# 02_ESP32-S2_Module.net
KiCad netlist of a schematic drawn in Altium Designer
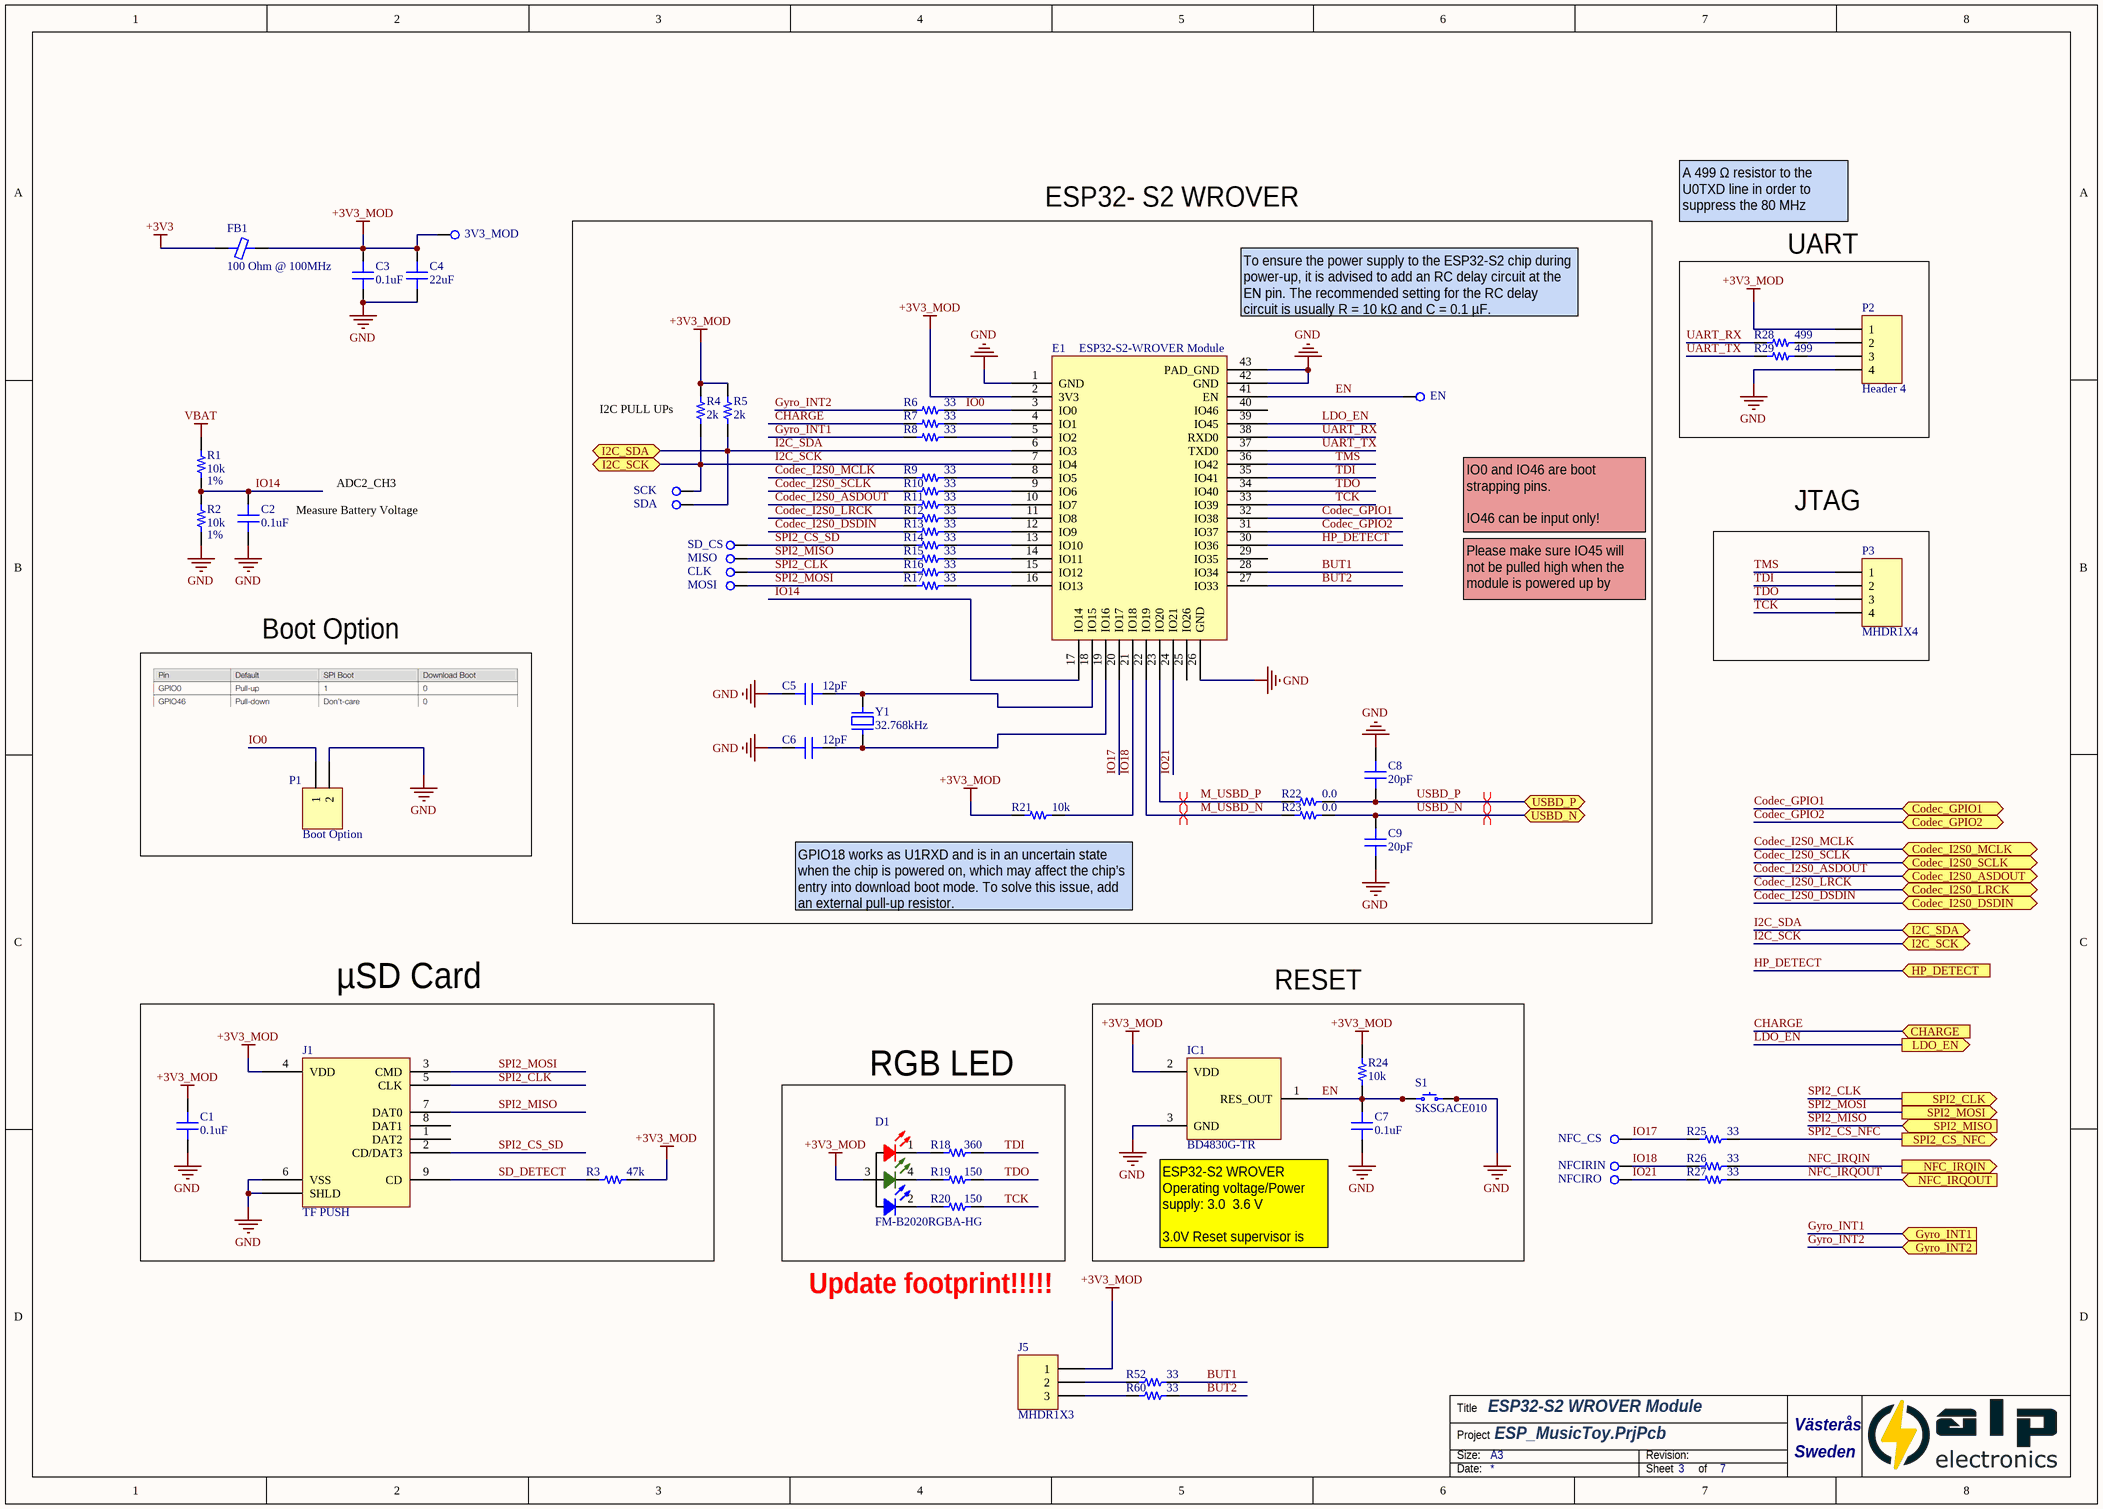
[diagram p0: [02] ESP32-S2 Module.SchDoc]

(export (version "E")
  (design (tool "Eeschema 10.0.6"))
  (components
    (comp (ref "3V3_MOD")
      (value "RCT-0C")
      (footprint "TE TP 0805")
      (description "0805 PROBE PAD")
      (fields (field (name "MANUFACTURER") "TE Connectivity AMP Connectors"))
      (libsource (lib "Celestial Library Database") (part "Test Point"))
    )
    (comp (ref "C1")
      (value "0.1uF")
      (footprint "CAP 0402/1005")
      (description "CAP CER 0.1UF 10V X7R 0402")
      (fields
        (field (name "PART NUMBER") "C1005X7R1A104K050BB")
        (field (name "MANUFACTURER") "TDK Corporation")
      )
      (libsource (lib "Celestial Library Database") (part "Capacitor"))
    )
    (comp (ref "C2")
      (value "0.1uF")
      (footprint "CAP 0402/1005")
      (description "CAP CER 0.1UF 10V X7R 0402")
      (fields
        (field (name "PART NUMBER") "C1005X7R1A104K050BB")
        (field (name "MANUFACTURER") "TDK Corporation")
      )
      (libsource (lib "Celestial Library Database") (part "Capacitor"))
    )
    (comp (ref "C3")
      (value "0.1uF")
      (footprint "CAP 0402/1005")
      (description "CAP CER 0.1UF 10V X7R 0402")
      (fields
        (field (name "PART NUMBER") "C1005X7R1A104K050BB")
        (field (name "MANUFACTURER") "TDK Corporation")
      )
      (libsource (lib "Celestial Library Database") (part "Capacitor"))
    )
    (comp (ref "C4")
      (value "22uF")
      (footprint "CAP 0603/1608")
      (description "CAP CER 22UF 10V X5R 0603")
      (fields
        (field (name "PART NUMBER") "C1608X5R1A226M080AC")
        (field (name "MANUFACTURER") "TDK Corporation")
      )
      (libsource (lib "Celestial Library Database") (part "Capacitor"))
    )
    (comp (ref "C5")
      (value "12pF")
      (footprint "CAP 0402/1005")
      (description "CAP CER 12PF 25V NP0 0402")
      (fields
        (field (name "PART NUMBER") "GRM1555C1E120JA01D")
        (field (name "MANUFACTURER") "Murata Electronics North America")
      )
      (libsource (lib "Celestial Library Database") (part "Capacitor"))
    )
    (comp (ref "C6")
      (value "12pF")
      (footprint "CAP 0402/1005")
      (description "CAP CER 12PF 25V NP0 0402")
      (fields
        (field (name "PART NUMBER") "GRM1555C1E120JA01D")
        (field (name "MANUFACTURER") "Murata Electronics North America")
      )
      (libsource (lib "Celestial Library Database") (part "Capacitor"))
    )
    (comp (ref "C7")
      (value "0.1uF")
      (footprint "CAP 0402/1005")
      (description "CAP CER 0.1UF 10V X7R 0402")
      (fields
        (field (name "PART NUMBER") "C1005X7R1A104K050BB")
        (field (name "MANUFACTURER") "TDK Corporation")
      )
      (libsource (lib "Celestial Library Database") (part "Capacitor"))
    )
    (comp (ref "C8")
      (value "20pF")
      (footprint "CAP 0402/1005")
      (description "CAP CER 20PF 25V NP0 0402")
      (fields
        (field (name "PART NUMBER") "GRM1555C1E200JA01D")
        (field (name "MANUFACTURER") "Murata Electronics North America")
      )
      (libsource (lib "Celestial Library Database") (part "Capacitor"))
    )
    (comp (ref "C9")
      (value "20pF")
      (footprint "CAP 0402/1005")
      (description "CAP CER 20PF 25V NP0 0402")
      (fields
        (field (name "PART NUMBER") "GRM1555C1E200JA01D")
        (field (name "MANUFACTURER") "Murata Electronics North America")
      )
      (libsource (lib "Celestial Library Database") (part "Capacitor"))
    )
    (comp (ref "CLK")
      (value "RCT-0C")
      (footprint "3D FootPrint_Backup:0.5mm-TestPad")
      (description "0805 PROBE PAD")
      (fields (field (name "MANUFACTURER") "TE Connectivity AMP Connectors"))
      (libsource (lib "Celestial Library Database") (part "Test Point"))
    )
    (comp (ref "D1")
      (value "FM-B2020RGBA-HG")
      (footprint "FM-B2020RGBA-HG")
      (description "RGB 615~630nmRed,515~535nmGreen,465~480nmBlue 2020")
      (fields (field (name "MANUFACTURER") "Foshan NationStar Optoelectronics"))
      (libsource (lib "Celestial Library Database") (part "RGB LED 4PIN"))
    )
    (comp (ref "E1")
      (value "ESP32-S2-WROVER Module")
      (footprint "ESP32-S2-WROVER")
      (libsource (lib "Altium Component") (part "ESP32-S2-WROVER Module"))
    )
    (comp (ref "EN")
      (value "RCT-0C")
      (footprint "3D FootPrint_Backup:0.5mm-TestPad")
      (description "0805 PROBE PAD")
      (fields (field (name "MANUFACTURER") "TE Connectivity AMP Connectors"))
      (libsource (lib "Celestial Library Database") (part "Test Point"))
    )
    (comp (ref "FB1")
      (value "100 Ohm @ 100MHz")
      (footprint "FER 0805/2012")
      (description "FERRITE CHIP 100 OHM 2000MA 0805")
      (fields
        (field (name "PART NUMBER") "CIC21P101NE")
        (field (name "MANUFACTURER") "Samsung Electro-Mechanics America, Inc.")
      )
      (libsource (lib "Celestial Library Database") (part "Ferrite Chip"))
    )
    (comp (ref "IC1")
      (value "BD4830G-TR")
      (footprint "TI SOT-23-5 DBV")
      (description "IC MPU RESET CIRC 3V SOT23-5")
      (fields (field (name "MANUFACTURER") "ROHM Semiconductor"))
      (libsource (lib "Celestial Library Database") (part "BD4830G"))
    )
    (comp (ref "J1")
      (value "TF PUSH")
      (footprint "TF-PUSH")
      (description "MICRO SD PUSH/PUSH SMALL 8C")
      (fields (field (name "MANUFACTURER") "SHOU HAN"))
      (libsource (lib "Celestial Library Database") (part "TF PUSH"))
    )
    (comp (ref "J5")
      (value "MHDR1X3")
      (footprint "MHDR1X3")
      (description "Header, 3-Pin")
      (fields (field (name "PUBLISHER") "Altium Limited"))
      (libsource (lib "Miscellaneous Connectors") (part "MHDR1X3"))
    )
    (comp (ref "MISO")
      (value "RCT-0C")
      (footprint "3D FootPrint_Backup:0.5mm-TestPad")
      (description "0805 PROBE PAD")
      (fields (field (name "MANUFACTURER") "TE Connectivity AMP Connectors"))
      (libsource (lib "Celestial Library Database") (part "Test Point"))
    )
    (comp (ref "MOSI")
      (value "RCT-0C")
      (footprint "3D FootPrint_Backup:0.5mm-TestPad")
      (description "0805 PROBE PAD")
      (fields (field (name "MANUFACTURER") "TE Connectivity AMP Connectors"))
      (libsource (lib "Celestial Library Database") (part "Test Point"))
    )
    (comp (ref "NFCIRIN")
      (value "RCT-0C")
      (footprint "3D FootPrint_Backup:0.5mm-TestPad")
      (description "0805 PROBE PAD")
      (fields (field (name "MANUFACTURER") "TE Connectivity AMP Connectors"))
      (libsource (lib "Celestial Library Database") (part "Test Point"))
    )
    (comp (ref "NFCIRO")
      (value "RCT-0C")
      (footprint "3D FootPrint_Backup:0.5mm-TestPad")
      (description "0805 PROBE PAD")
      (fields (field (name "MANUFACTURER") "TE Connectivity AMP Connectors"))
      (libsource (lib "Celestial Library Database") (part "Test Point"))
    )
    (comp (ref "NFC_CS")
      (value "RCT-0C")
      (footprint "3D FootPrint_Backup:0.5mm-TestPad")
      (description "0805 PROBE PAD")
      (fields (field (name "MANUFACTURER") "TE Connectivity AMP Connectors"))
      (libsource (lib "Celestial Library Database") (part "Test Point"))
    )
    (comp (ref "P1")
      (value "Boot Option")
      (footprint "HDR1X2")
      (description "Header, 2-Pin")
      (fields (field (name "PUBLISHER") "Altium Limited"))
      (libsource (lib "Miscellaneous Connectors") (part "Header 2"))
    )
    (comp (ref "P2")
      (value "Header 4")
      (footprint "HDR1X4")
      (description "Header, 4-Pin")
      (fields (field (name "PUBLISHER") "Altium Limited"))
      (libsource (lib "Miscellaneous Connectors") (part "Header 4"))
    )
    (comp (ref "P3")
      (value "MHDR1X4")
      (footprint "MHDR1X4")
      (description "Header, 4-Pin")
      (fields (field (name "PUBLISHER") "Altium Limited"))
      (libsource (lib "Miscellaneous Connectors") (part "MHDR1X4"))
    )
    (comp (ref "R1")
      (value "10k")
      (footprint "RES 0402/1005")
      (description "RES SMD 10K OHM 1% 1/10W 0402")
      (fields
        (field (name "PART NUMBER") "ERJ-2RKF1002X")
        (field (name "MANUFACTURER") "Panasonic Electronic Components")
        (field (name "TOLERANCE") "1%")
      )
      (libsource (lib "Celestial Library Database") (part "Resistor"))
    )
    (comp (ref "R2")
      (value "10k")
      (footprint "RES 0402/1005")
      (description "RES SMD 10K OHM 1% 1/10W 0402")
      (fields
        (field (name "PART NUMBER") "ERJ-2RKF1002X")
        (field (name "MANUFACTURER") "Panasonic Electronic Components")
        (field (name "TOLERANCE") "1%")
      )
      (libsource (lib "Celestial Library Database") (part "Resistor"))
    )
    (comp (ref "R3")
      (value "47k")
      (footprint "RES 0402/1005")
      (description "RES SMD 47K OHM 5% 1/16W 0402")
      (fields (field (name "PART NUMBER") "RC0402JR-0747KL") (field (name "MANUFACTURER") "Yageo"))
      (libsource (lib "Celestial Library Database") (part "Resistor"))
    )
    (comp (ref "R4")
      (value "2k")
      (footprint "RES 0402/1005")
      (description "RES SMD 2K OHM 5% 1/10W 0402")
      (fields
        (field (name "PART NUMBER") "ERJ-2GEJ202X")
        (field (name "MANUFACTURER") "Panasonic Electronic Components")
      )
      (libsource (lib "Celestial Library Database") (part "Resistor"))
    )
    (comp (ref "R5")
      (value "2k")
      (footprint "RES 0402/1005")
      (description "RES SMD 2K OHM 5% 1/10W 0402")
      (fields
        (field (name "PART NUMBER") "ERJ-2GEJ202X")
        (field (name "MANUFACTURER") "Panasonic Electronic Components")
      )
      (libsource (lib "Celestial Library Database") (part "Resistor"))
    )
    (comp (ref "R6")
      (value "33")
      (footprint "RES 0402/1005")
      (description "RES SMD 33 OHM 5% 1/10W 0402")
      (fields
        (field (name "PART NUMBER") "ERJ-2GEJ330X")
        (field (name "MANUFACTURER") "Panasonic Electronic Components")
      )
      (libsource (lib "Celestial Library Database") (part "Resistor"))
    )
    (comp (ref "R7")
      (value "33")
      (footprint "RES 0402/1005")
      (description "RES SMD 33 OHM 5% 1/10W 0402")
      (fields
        (field (name "PART NUMBER") "ERJ-2GEJ330X")
        (field (name "MANUFACTURER") "Panasonic Electronic Components")
      )
      (libsource (lib "Celestial Library Database") (part "Resistor"))
    )
    (comp (ref "R8")
      (value "33")
      (footprint "RES 0402/1005")
      (description "RES SMD 33 OHM 5% 1/10W 0402")
      (fields
        (field (name "PART NUMBER") "ERJ-2GEJ330X")
        (field (name "MANUFACTURER") "Panasonic Electronic Components")
      )
      (libsource (lib "Celestial Library Database") (part "Resistor"))
    )
    (comp (ref "R9")
      (value "33")
      (footprint "RES 0402/1005")
      (description "RES SMD 33 OHM 5% 1/10W 0402")
      (fields
        (field (name "PART NUMBER") "ERJ-2GEJ330X")
        (field (name "MANUFACTURER") "Panasonic Electronic Components")
      )
      (libsource (lib "Celestial Library Database") (part "Resistor"))
    )
    (comp (ref "R10")
      (value "33")
      (footprint "RES 0402/1005")
      (description "RES SMD 33 OHM 5% 1/10W 0402")
      (fields
        (field (name "PART NUMBER") "ERJ-2GEJ330X")
        (field (name "MANUFACTURER") "Panasonic Electronic Components")
      )
      (libsource (lib "Celestial Library Database") (part "Resistor"))
    )
    (comp (ref "R11")
      (value "33")
      (footprint "RES 0402/1005")
      (description "RES SMD 33 OHM 5% 1/10W 0402")
      (fields
        (field (name "PART NUMBER") "ERJ-2GEJ330X")
        (field (name "MANUFACTURER") "Panasonic Electronic Components")
      )
      (libsource (lib "Celestial Library Database") (part "Resistor"))
    )
    (comp (ref "R12")
      (value "33")
      (footprint "RES 0402/1005")
      (description "RES SMD 33 OHM 5% 1/10W 0402")
      (fields
        (field (name "PART NUMBER") "ERJ-2GEJ330X")
        (field (name "MANUFACTURER") "Panasonic Electronic Components")
      )
      (libsource (lib "Celestial Library Database") (part "Resistor"))
    )
    (comp (ref "R13")
      (value "33")
      (footprint "RES 0402/1005")
      (description "RES SMD 33 OHM 5% 1/10W 0402")
      (fields
        (field (name "PART NUMBER") "ERJ-2GEJ330X")
        (field (name "MANUFACTURER") "Panasonic Electronic Components")
      )
      (libsource (lib "Celestial Library Database") (part "Resistor"))
    )
    (comp (ref "R14")
      (value "33")
      (footprint "RES 0402/1005")
      (description "RES SMD 33 OHM 5% 1/10W 0402")
      (fields
        (field (name "PART NUMBER") "ERJ-2GEJ330X")
        (field (name "MANUFACTURER") "Panasonic Electronic Components")
      )
      (libsource (lib "Celestial Library Database") (part "Resistor"))
    )
    (comp (ref "R15")
      (value "33")
      (footprint "RES 0402/1005")
      (description "RES SMD 33 OHM 5% 1/10W 0402")
      (fields
        (field (name "PART NUMBER") "ERJ-2GEJ330X")
        (field (name "MANUFACTURER") "Panasonic Electronic Components")
      )
      (libsource (lib "Celestial Library Database") (part "Resistor"))
    )
    (comp (ref "R16")
      (value "33")
      (footprint "RES 0402/1005")
      (description "RES SMD 33 OHM 5% 1/10W 0402")
      (fields
        (field (name "PART NUMBER") "ERJ-2GEJ330X")
        (field (name "MANUFACTURER") "Panasonic Electronic Components")
      )
      (libsource (lib "Celestial Library Database") (part "Resistor"))
    )
    (comp (ref "R17")
      (value "33")
      (footprint "RES 0402/1005")
      (description "RES SMD 33 OHM 5% 1/10W 0402")
      (fields
        (field (name "PART NUMBER") "ERJ-2GEJ330X")
        (field (name "MANUFACTURER") "Panasonic Electronic Components")
      )
      (libsource (lib "Celestial Library Database") (part "Resistor"))
    )
    (comp (ref "R18")
      (value "360")
      (footprint "RES 0402/1005")
      (description "RES SMD 360 OHM 5% 1/16W 0402")
      (fields (field (name "PART NUMBER") "RC0402JR-07360RL") (field (name "MANUFACTURER") "Yageo"))
      (libsource (lib "Celestial Library Database") (part "Resistor"))
    )
    (comp (ref "R19")
      (value "150")
      (footprint "RES 0402/1005")
      (description "RES SMD 150 OHM 5% 1/16W 0402")
      (fields (field (name "PART NUMBER") "RC0402JR-07150RL") (field (name "MANUFACTURER") "Yageo"))
      (libsource (lib "Celestial Library Database") (part "Resistor"))
    )
    (comp (ref "R20")
      (value "150")
      (footprint "RES 0402/1005")
      (description "RES SMD 150 OHM 5% 1/16W 0402")
      (fields (field (name "PART NUMBER") "RC0402JR-07150RL") (field (name "MANUFACTURER") "Yageo"))
      (libsource (lib "Celestial Library Database") (part "Resistor"))
    )
    (comp (ref "R21")
      (value "10k")
      (footprint "RES 0402/1005")
      (description "RES SMD 10K OHM 5% 1/16W 0402")
      (fields (field (name "PART NUMBER") "RC0402JR-0710KL") (field (name "MANUFACTURER") "Yageo"))
      (libsource (lib "Celestial Library Database") (part "Resistor"))
    )
    (comp (ref "R22")
      (value "0.0")
      (footprint "RES 0402/1005")
      (description "RES SMD 0.0OHM JUMPER 1/16W 0402")
      (fields (field (name "PART NUMBER") "AC0402JR-070RL") (field (name "MANUFACTURER") "Yageo"))
      (libsource (lib "Celestial Library Database") (part "Resistor"))
    )
    (comp (ref "R23")
      (value "0.0")
      (footprint "RES 0402/1005")
      (description "RES SMD 0.0OHM JUMPER 1/16W 0402")
      (fields (field (name "PART NUMBER") "AC0402JR-070RL") (field (name "MANUFACTURER") "Yageo"))
      (libsource (lib "Celestial Library Database") (part "Resistor"))
    )
    (comp (ref "R24")
      (value "10k")
      (footprint "RES 0402/1005")
      (description "RES SMD 10K OHM 5% 1/16W 0402")
      (fields (field (name "PART NUMBER") "RC0402JR-0710KL") (field (name "MANUFACTURER") "Yageo"))
      (libsource (lib "Celestial Library Database") (part "Resistor"))
    )
    (comp (ref "R25")
      (value "33")
      (footprint "RES 0402/1005")
      (description "RES SMD 33 OHM 5% 1/10W 0402")
      (fields
        (field (name "PART NUMBER") "ERJ-2GEJ330X")
        (field (name "MANUFACTURER") "Panasonic Electronic Components")
      )
      (libsource (lib "Celestial Library Database") (part "Resistor"))
    )
    (comp (ref "R26")
      (value "33")
      (footprint "RES 0402/1005")
      (description "RES SMD 33 OHM 5% 1/10W 0402")
      (fields
        (field (name "PART NUMBER") "ERJ-2GEJ330X")
        (field (name "MANUFACTURER") "Panasonic Electronic Components")
      )
      (libsource (lib "Celestial Library Database") (part "Resistor"))
    )
    (comp (ref "R27")
      (value "33")
      (footprint "RES 0402/1005")
      (description "RES SMD 33 OHM 5% 1/10W 0402")
      (fields
        (field (name "PART NUMBER") "ERJ-2GEJ330X")
        (field (name "MANUFACTURER") "Panasonic Electronic Components")
      )
      (libsource (lib "Celestial Library Database") (part "Resistor"))
    )
    (comp (ref "R28")
      (value "499")
      (footprint "RES 0402/1005")
      (description "RES SMD 499 OHM 1% 1/10W 0402")
      (fields
        (field (name "PART NUMBER") "ERJ-2RKF4990X")
        (field (name "MANUFACTURER") "Panasonic Electronic Components")
      )
      (libsource (lib "Celestial Library Database") (part "Resistor"))
    )
    (comp (ref "R29")
      (value "499")
      (footprint "RES 0402/1005")
      (description "RES SMD 499 OHM 1% 1/10W 0402")
      (fields
        (field (name "PART NUMBER") "ERJ-2RKF4990X")
        (field (name "MANUFACTURER") "Panasonic Electronic Components")
      )
      (libsource (lib "Celestial Library Database") (part "Resistor"))
    )
    (comp (ref "R52")
      (value "33")
      (footprint "RES 0402/1005")
      (description "RES SMD 33 OHM 5% 1/10W 0402")
      (fields
        (field (name "PART NUMBER") "ERJ-2GEJ330X")
        (field (name "MANUFACTURER") "Panasonic Electronic Components")
      )
      (libsource (lib "Celestial Library Database") (part "Resistor"))
    )
    (comp (ref "R60")
      (value "33")
      (footprint "RES 0402/1005")
      (description "RES SMD 33 OHM 5% 1/10W 0402")
      (fields
        (field (name "PART NUMBER") "ERJ-2GEJ330X")
        (field (name "MANUFACTURER") "Panasonic Electronic Components")
      )
      (libsource (lib "Celestial Library Database") (part "Resistor"))
    )
    (comp (ref "S1")
      (value "SKSGACE010")
      (footprint "SKSGACE010")
      (description "SWITCH TACTILE SPST-NO 0.05A 16V")
      (fields (field (name "MANUFACTURER") "ALPS"))
      (libsource (lib "Celestial Library Database") (part "SPST-NO 4 PIN"))
    )
    (comp (ref "SCK")
      (value "RCT-0C")
      (footprint "3D FootPrint_Backup:0.5mm-TestPad")
      (description "0805 PROBE PAD")
      (fields (field (name "MANUFACTURER") "TE Connectivity AMP Connectors"))
      (libsource (lib "Celestial Library Database") (part "Test Point"))
    )
    (comp (ref "SDA")
      (value "RCT-0C")
      (footprint "3D FootPrint_Backup:0.5mm-TestPad")
      (description "0805 PROBE PAD")
      (fields (field (name "MANUFACTURER") "TE Connectivity AMP Connectors"))
      (libsource (lib "Celestial Library Database") (part "Test Point"))
    )
    (comp (ref "SD_CS")
      (value "RCT-0C")
      (footprint "3D FootPrint_Backup:0.5mm-TestPad")
      (description "0805 PROBE PAD")
      (fields (field (name "MANUFACTURER") "TE Connectivity AMP Connectors"))
      (libsource (lib "Celestial Library Database") (part "Test Point"))
    )
    (comp (ref "Y1")
      (value "32.768kHz")
      (footprint "ABRACON ABS07")
      (description "CRYSTAL 32.7680KHZ 12.5PF SMD")
      (fields (field (name "PART NUMBER") "ABS07-32.768KHZ-T") (field (name "MANUFACTURER") "Abracon LLC"))
      (libsource (lib "Celestial Library Database") (part "Abracon Crystal ABS07"))
    )
  )
  (nets
    (net (code "1") (name "+3V3") (class "Default")
      (node (ref "FB1") (pin "1") (pinfunction "1_1") (pintype "passive"))
    )
    (net (code "2") (name "+3V3_MOD") (class "Default")
      (node (ref "3V3_MOD") (pin "1") (pinfunction "TP_1") (pintype "passive"))
      (node (ref "C1") (pin "2") (pinfunction "2_2") (pintype "passive"))
      (node (ref "C3") (pin "2") (pinfunction "2_2") (pintype "passive"))
      (node (ref "C4") (pin "2") (pinfunction "2_2") (pintype "passive"))
      (node (ref "D1") (pin "3") (pinfunction "3_3") (pintype "passive"))
      (node (ref "E1") (pin "2") (pinfunction "3V3_2") (pintype "passive"))
      (node (ref "FB1") (pin "2") (pinfunction "2_2") (pintype "passive"))
      (node (ref "IC1") (pin "2") (pinfunction "VDD_2") (pintype "passive"))
      (node (ref "J1") (pin "4") (pinfunction "VDD_4") (pintype "passive"))
      (node (ref "J5") (pin "1") (pinfunction "1_1") (pintype "passive"))
      (node (ref "P2") (pin "1") (pinfunction "1_1") (pintype "passive"))
      (node (ref "R21") (pin "1") (pinfunction "1_1") (pintype "passive"))
      (node (ref "R24") (pin "2") (pinfunction "2_2") (pintype "passive"))
      (node (ref "R3") (pin "2") (pinfunction "2_2") (pintype "passive"))
      (node (ref "R4") (pin "2") (pinfunction "2_2") (pintype "passive"))
      (node (ref "R5") (pin "2") (pinfunction "2_2") (pintype "passive"))
    )
    (net (code "3") (name "/BUT1") (class "Default")
      (node (ref "E1") (pin "28") (pinfunction "IO34_28") (pintype "passive"))
      (node (ref "R52") (pin "2") (pinfunction "2_2") (pintype "passive"))
    )
    (net (code "4") (name "/BUT2") (class "Default")
      (node (ref "E1") (pin "27") (pinfunction "IO33_27") (pintype "passive"))
      (node (ref "R60") (pin "2") (pinfunction "2_2") (pintype "passive"))
    )
    (net (code "5") (name "/CHARGE") (class "Default")
      (node (ref "R7") (pin "1") (pinfunction "1_1") (pintype "passive"))
    )
    (net (code "6") (name "/Codec_GPIO1") (class "Default")
      (node (ref "E1") (pin "32") (pinfunction "IO38_32") (pintype "passive"))
    )
    (net (code "7") (name "/Codec_GPIO2") (class "Default")
      (node (ref "E1") (pin "31") (pinfunction "IO37_31") (pintype "passive"))
    )
    (net (code "8") (name "/Codec_I2S0_ASDOUT") (class "Default")
      (node (ref "R11") (pin "1") (pinfunction "1_1") (pintype "passive"))
    )
    (net (code "9") (name "/Codec_I2S0_DSDIN") (class "Default")
      (node (ref "R13") (pin "1") (pinfunction "1_1") (pintype "passive"))
    )
    (net (code "10") (name "/Codec_I2S0_LRCK") (class "Default")
      (node (ref "R12") (pin "1") (pinfunction "1_1") (pintype "passive"))
    )
    (net (code "11") (name "/Codec_I2S0_MCLK") (class "Default")
      (node (ref "R9") (pin "1") (pinfunction "1_1") (pintype "passive"))
    )
    (net (code "12") (name "/Codec_I2S0_SCLK") (class "Default")
      (node (ref "R10") (pin "1") (pinfunction "1_1") (pintype "passive"))
    )
    (net (code "13") (name "/EN") (class "Default")
      (node (ref "C7") (pin "2") (pinfunction "2_2") (pintype "passive"))
      (node (ref "E1") (pin "41") (pinfunction "EN_41") (pintype "passive"))
      (node (ref "EN") (pin "1") (pinfunction "TP_1") (pintype "passive"))
      (node (ref "IC1") (pin "1") (pinfunction "RES_OUT_1") (pintype "passive"))
      (node (ref "R24") (pin "1") (pinfunction "1_1") (pintype "passive"))
      (node (ref "S1") (pin "1") (pinfunction "1_1") (pintype "passive"))
      (node (ref "S1") (pin "2") (pinfunction "2_2") (pintype "passive"))
    )
    (net (code "14") (name "/Gyro_INT1") (class "Default")
      (node (ref "R8") (pin "1") (pinfunction "1_1") (pintype "passive"))
    )
    (net (code "15") (name "/Gyro_INT2") (class "Default")
      (node (ref "R6") (pin "1") (pinfunction "1_1") (pintype "passive"))
    )
    (net (code "16") (name "/HP_DETECT") (class "Default")
      (node (ref "E1") (pin "30") (pinfunction "IO36_30") (pintype "passive"))
    )
    (net (code "17") (name "/I2C_SCK") (class "Default")
      (node (ref "E1") (pin "7") (pinfunction "IO4_7") (pintype "passive"))
      (node (ref "R4") (pin "1") (pinfunction "1_1") (pintype "passive"))
      (node (ref "SCK") (pin "1") (pinfunction "TP_1") (pintype "passive"))
    )
    (net (code "18") (name "/I2C_SDA") (class "Default")
      (node (ref "E1") (pin "6") (pinfunction "IO3_6") (pintype "passive"))
      (node (ref "R5") (pin "1") (pinfunction "1_1") (pintype "passive"))
      (node (ref "SDA") (pin "1") (pinfunction "TP_1") (pintype "passive"))
    )
    (net (code "19") (name "/IO0") (class "Default")
      (node (ref "E1") (pin "3") (pinfunction "IO0_3") (pintype "passive"))
      (node (ref "P1") (pin "1") (pinfunction "1_1") (pintype "passive"))
      (node (ref "R6") (pin "2") (pinfunction "2_2") (pintype "passive"))
    )
    (net (code "20") (name "/IO14") (class "Default")
      (node (ref "C2") (pin "2") (pinfunction "2_2") (pintype "passive"))
      (node (ref "E1") (pin "17") (pinfunction "IO14_17") (pintype "passive"))
      (node (ref "R1") (pin "1") (pinfunction "1_1") (pintype "passive"))
      (node (ref "R2") (pin "2") (pinfunction "2_2") (pintype "passive"))
    )
    (net (code "21") (name "/IO17") (class "Default")
      (node (ref "E1") (pin "20") (pinfunction "IO17_20") (pintype "passive"))
      (node (ref "NFC_CS") (pin "1") (pinfunction "TP_1") (pintype "passive"))
      (node (ref "R25") (pin "1") (pinfunction "1_1") (pintype "passive"))
    )
    (net (code "22") (name "/IO18") (class "Default")
      (node (ref "E1") (pin "21") (pinfunction "IO18_21") (pintype "passive"))
      (node (ref "NFCIRIN") (pin "1") (pinfunction "TP_1") (pintype "passive"))
      (node (ref "R21") (pin "2") (pinfunction "2_2") (pintype "passive"))
      (node (ref "R26") (pin "1") (pinfunction "1_1") (pintype "passive"))
    )
    (net (code "23") (name "/IO21") (class "Default")
      (node (ref "E1") (pin "24") (pinfunction "IO21_24") (pintype "passive"))
      (node (ref "NFCIRO") (pin "1") (pinfunction "TP_1") (pintype "passive"))
      (node (ref "R27") (pin "1") (pinfunction "1_1") (pintype "passive"))
    )
    (net (code "24") (name "/LDO_EN") (class "Default")
      (node (ref "E1") (pin "39") (pinfunction "IO45_39") (pintype "passive"))
    )
    (net (code "25") (name "/M_USBD_N") (class "Default")
      (node (ref "E1") (pin "22") (pinfunction "IO19_22") (pintype "passive"))
      (node (ref "R23") (pin "1") (pinfunction "1_1") (pintype "passive"))
    )
    (net (code "26") (name "/M_USBD_P") (class "Default")
      (node (ref "E1") (pin "23") (pinfunction "IO20_23") (pintype "passive"))
      (node (ref "R22") (pin "1") (pinfunction "1_1") (pintype "passive"))
    )
    (net (code "27") (name "/NFC_IRQIN") (class "Default")
      (node (ref "R26") (pin "2") (pinfunction "2_2") (pintype "passive"))
    )
    (net (code "28") (name "/NFC_IRQOUT") (class "Default")
      (node (ref "R27") (pin "2") (pinfunction "2_2") (pintype "passive"))
    )
    (net (code "29") (name "/SD_DETECT") (class "Default")
      (node (ref "J1") (pin "9") (pinfunction "CD_9") (pintype "passive"))
      (node (ref "R3") (pin "1") (pinfunction "1_1") (pintype "passive"))
    )
    (net (code "30") (name "/SPI2_CLK") (class "Default")
      (node (ref "CLK") (pin "1") (pinfunction "TP_1") (pintype "passive"))
      (node (ref "J1") (pin "5") (pinfunction "CLK_5") (pintype "passive"))
      (node (ref "R16") (pin "1") (pinfunction "1_1") (pintype "passive"))
    )
    (net (code "31") (name "/SPI2_CS_NFC") (class "Default")
      (node (ref "R25") (pin "2") (pinfunction "2_2") (pintype "passive"))
    )
    (net (code "32") (name "/SPI2_CS_SD") (class "Default")
      (node (ref "J1") (pin "2") (pinfunction "CD/DAT3_2") (pintype "passive"))
      (node (ref "R14") (pin "1") (pinfunction "1_1") (pintype "passive"))
      (node (ref "SD_CS") (pin "1") (pinfunction "TP_1") (pintype "passive"))
    )
    (net (code "33") (name "/SPI2_MISO") (class "Default")
      (node (ref "J1") (pin "7") (pinfunction "DAT0_7") (pintype "passive"))
      (node (ref "MISO") (pin "1") (pinfunction "TP_1") (pintype "passive"))
      (node (ref "R15") (pin "1") (pinfunction "1_1") (pintype "passive"))
    )
    (net (code "34") (name "/SPI2_MOSI") (class "Default")
      (node (ref "J1") (pin "3") (pinfunction "CMD_3") (pintype "passive"))
      (node (ref "MOSI") (pin "1") (pinfunction "TP_1") (pintype "passive"))
      (node (ref "R17") (pin "1") (pinfunction "1_1") (pintype "passive"))
    )
    (net (code "35") (name "/TCK") (class "Default")
      (node (ref "E1") (pin "33") (pinfunction "IO39_33") (pintype "passive"))
      (node (ref "P3") (pin "4") (pinfunction "4_4") (pintype "passive"))
      (node (ref "R20") (pin "2") (pinfunction "2_2") (pintype "passive"))
    )
    (net (code "36") (name "/TDI") (class "Default")
      (node (ref "E1") (pin "35") (pinfunction "IO41_35") (pintype "passive"))
      (node (ref "P3") (pin "2") (pinfunction "2_2") (pintype "passive"))
      (node (ref "R18") (pin "2") (pinfunction "2_2") (pintype "passive"))
    )
    (net (code "37") (name "/TDO") (class "Default")
      (node (ref "E1") (pin "34") (pinfunction "IO40_34") (pintype "passive"))
      (node (ref "P3") (pin "3") (pinfunction "3_3") (pintype "passive"))
      (node (ref "R19") (pin "2") (pinfunction "2_2") (pintype "passive"))
    )
    (net (code "38") (name "/TMS") (class "Default")
      (node (ref "E1") (pin "36") (pinfunction "IO42_36") (pintype "passive"))
      (node (ref "P3") (pin "1") (pinfunction "1_1") (pintype "passive"))
    )
    (net (code "39") (name "/UART_RX") (class "Default")
      (node (ref "E1") (pin "38") (pinfunction "RXD0_38") (pintype "passive"))
      (node (ref "R28") (pin "1") (pinfunction "1_1") (pintype "passive"))
    )
    (net (code "40") (name "/UART_TX") (class "Default")
      (node (ref "E1") (pin "37") (pinfunction "TXD0_37") (pintype "passive"))
      (node (ref "R29") (pin "1") (pinfunction "1_1") (pintype "passive"))
    )
    (net (code "41") (name "/USBD_N") (class "Default")
      (node (ref "C9") (pin "2") (pinfunction "2_2") (pintype "passive"))
      (node (ref "R23") (pin "2") (pinfunction "2_2") (pintype "passive"))
    )
    (net (code "42") (name "/USBD_P") (class "Default")
      (node (ref "C8") (pin "1") (pinfunction "1_1") (pintype "passive"))
      (node (ref "R22") (pin "2") (pinfunction "2_2") (pintype "passive"))
    )
    (net (code "43") (name "GND") (class "Default")
      (node (ref "C1") (pin "1") (pinfunction "1_1") (pintype "passive"))
      (node (ref "C2") (pin "1") (pinfunction "1_1") (pintype "passive"))
      (node (ref "C3") (pin "1") (pinfunction "1_1") (pintype "passive"))
      (node (ref "C4") (pin "1") (pinfunction "1_1") (pintype "passive"))
      (node (ref "C5") (pin "1") (pinfunction "1_1") (pintype "passive"))
      (node (ref "C6") (pin "1") (pinfunction "1_1") (pintype "passive"))
      (node (ref "C7") (pin "1") (pinfunction "1_1") (pintype "passive"))
      (node (ref "C8") (pin "2") (pinfunction "2_2") (pintype "passive"))
      (node (ref "C9") (pin "1") (pinfunction "1_1") (pintype "passive"))
      (node (ref "E1") (pin "1") (pinfunction "GND_1") (pintype "passive"))
      (node (ref "E1") (pin "26") (pinfunction "GND_26") (pintype "passive"))
      (node (ref "E1") (pin "42") (pinfunction "GND_42") (pintype "passive"))
      (node (ref "E1") (pin "43") (pinfunction "PAD_GND_43") (pintype "passive"))
      (node (ref "IC1") (pin "3") (pinfunction "GND_3") (pintype "passive"))
      (node (ref "J1") (pin "6") (pinfunction "VSS_6") (pintype "passive"))
      (node (ref "J1") (pin "G") (pinfunction "SHLD_G") (pintype "passive"))
      (node (ref "P1") (pin "2") (pinfunction "2_2") (pintype "passive"))
      (node (ref "P2") (pin "4") (pinfunction "4_4") (pintype "passive"))
      (node (ref "R2") (pin "1") (pinfunction "1_1") (pintype "passive"))
      (node (ref "S1") (pin "3") (pinfunction "3_3") (pintype "passive"))
      (node (ref "S1") (pin "4") (pinfunction "4_4") (pintype "passive"))
    )
    (net (code "44") (name "Net-(D1-Pad1)") (class "Default")
      (node (ref "D1") (pin "1") (pinfunction "1_1") (pintype "passive"))
      (node (ref "R18") (pin "1") (pinfunction "1_1") (pintype "passive"))
    )
    (net (code "45") (name "Net-(D1-Pad2)") (class "Default")
      (node (ref "D1") (pin "2") (pinfunction "2_2") (pintype "passive"))
      (node (ref "R20") (pin "1") (pinfunction "1_1") (pintype "passive"))
    )
    (net (code "46") (name "Net-(D1-Pad4)") (class "Default")
      (node (ref "D1") (pin "4") (pinfunction "4_4") (pintype "passive"))
      (node (ref "R19") (pin "1") (pinfunction "1_1") (pintype "passive"))
    )
    (net (code "47") (name "Net-(E1-IO1)") (class "Default")
      (node (ref "E1") (pin "4") (pinfunction "IO1_4") (pintype "passive"))
      (node (ref "R7") (pin "2") (pinfunction "2_2") (pintype "passive"))
    )
    (net (code "48") (name "Net-(E1-IO2)") (class "Default")
      (node (ref "E1") (pin "5") (pinfunction "IO2_5") (pintype "passive"))
      (node (ref "R8") (pin "2") (pinfunction "2_2") (pintype "passive"))
    )
    (net (code "49") (name "Net-(E1-IO5)") (class "Default")
      (node (ref "E1") (pin "8") (pinfunction "IO5_8") (pintype "passive"))
      (node (ref "R9") (pin "2") (pinfunction "2_2") (pintype "passive"))
    )
    (net (code "50") (name "Net-(E1-IO6)") (class "Default")
      (node (ref "E1") (pin "9") (pinfunction "IO6_9") (pintype "passive"))
      (node (ref "R10") (pin "2") (pinfunction "2_2") (pintype "passive"))
    )
    (net (code "51") (name "Net-(E1-IO7)") (class "Default")
      (node (ref "E1") (pin "10") (pinfunction "IO7_10") (pintype "passive"))
      (node (ref "R11") (pin "2") (pinfunction "2_2") (pintype "passive"))
    )
    (net (code "52") (name "Net-(E1-IO8)") (class "Default")
      (node (ref "E1") (pin "11") (pinfunction "IO8_11") (pintype "passive"))
      (node (ref "R12") (pin "2") (pinfunction "2_2") (pintype "passive"))
    )
    (net (code "53") (name "Net-(E1-IO9)") (class "Default")
      (node (ref "E1") (pin "12") (pinfunction "IO9_12") (pintype "passive"))
      (node (ref "R13") (pin "2") (pinfunction "2_2") (pintype "passive"))
    )
    (net (code "54") (name "Net-(E1-IO10)") (class "Default")
      (node (ref "E1") (pin "13") (pinfunction "IO10_13") (pintype "passive"))
      (node (ref "R14") (pin "2") (pinfunction "2_2") (pintype "passive"))
    )
    (net (code "55") (name "Net-(E1-IO11)") (class "Default")
      (node (ref "E1") (pin "14") (pinfunction "IO11_14") (pintype "passive"))
      (node (ref "R15") (pin "2") (pinfunction "2_2") (pintype "passive"))
    )
    (net (code "56") (name "Net-(E1-IO12)") (class "Default")
      (node (ref "E1") (pin "15") (pinfunction "IO12_15") (pintype "passive"))
      (node (ref "R16") (pin "2") (pinfunction "2_2") (pintype "passive"))
    )
    (net (code "57") (name "Net-(E1-IO13)") (class "Default")
      (node (ref "E1") (pin "16") (pinfunction "IO13_16") (pintype "passive"))
      (node (ref "R17") (pin "2") (pinfunction "2_2") (pintype "passive"))
    )
    (net (code "58") (name "Net-(E1-IO15)") (class "Default")
      (node (ref "C5") (pin "2") (pinfunction "2_2") (pintype "passive"))
      (node (ref "E1") (pin "18") (pinfunction "IO15_18") (pintype "passive"))
      (node (ref "Y1") (pin "2") (pinfunction "2_2") (pintype "passive"))
    )
    (net (code "59") (name "Net-(E1-IO16)") (class "Default")
      (node (ref "C6") (pin "2") (pinfunction "2_2") (pintype "passive"))
      (node (ref "E1") (pin "19") (pinfunction "IO16_19") (pintype "passive"))
      (node (ref "Y1") (pin "1") (pinfunction "1_1") (pintype "passive"))
    )
    (net (code "60") (name "Net-(J5-Pad2)") (class "Default")
      (node (ref "J5") (pin "2") (pinfunction "2_2") (pintype "passive"))
      (node (ref "R52") (pin "1") (pinfunction "1_1") (pintype "passive"))
    )
    (net (code "61") (name "Net-(J5-Pad3)") (class "Default")
      (node (ref "J5") (pin "3") (pinfunction "3_3") (pintype "passive"))
      (node (ref "R60") (pin "1") (pinfunction "1_1") (pintype "passive"))
    )
    (net (code "62") (name "Net-(P2-Pad2)") (class "Default")
      (node (ref "P2") (pin "2") (pinfunction "2_2") (pintype "passive"))
      (node (ref "R28") (pin "2") (pinfunction "2_2") (pintype "passive"))
    )
    (net (code "63") (name "Net-(P2-Pad3)") (class "Default")
      (node (ref "P2") (pin "3") (pinfunction "3_3") (pintype "passive"))
      (node (ref "R29") (pin "2") (pinfunction "2_2") (pintype "passive"))
    )
    (net (code "64") (name "VBAT") (class "Default")
      (node (ref "R1") (pin "2") (pinfunction "2_2") (pintype "passive"))
    )
    (net (code "65") (name "unconnected-(E1-IO26-Pad25)") (class "Default")
      (node (ref "E1") (pin "25") (pinfunction "IO26_25") (pintype "passive"))
    )
    (net (code "66") (name "unconnected-(E1-IO35-Pad29)") (class "Default")
      (node (ref "E1") (pin "29") (pinfunction "IO35_29") (pintype "passive"))
    )
    (net (code "67") (name "unconnected-(E1-IO46-Pad40)") (class "Default")
      (node (ref "E1") (pin "40") (pinfunction "IO46_40") (pintype "passive"))
    )
    (net (code "68") (name "unconnected-(IC1-NC-Pad4)") (class "Default")
      (node (ref "IC1") (pin "4") (pinfunction "NC_4") (pintype "passive"))
    )
    (net (code "69") (name "unconnected-(IC1-NC-Pad5)") (class "Default")
      (node (ref "IC1") (pin "5") (pinfunction "NC_5") (pintype "passive"))
    )
    (net (code "70") (name "unconnected-(J1-DAT1-Pad8)") (class "Default")
      (node (ref "J1") (pin "8") (pinfunction "DAT1_8") (pintype "passive"))
    )
    (net (code "71") (name "unconnected-(J1-DAT2-Pad1)") (class "Default")
      (node (ref "J1") (pin "1") (pinfunction "DAT2_1") (pintype "passive"))
    )
  )
)
